# Audio.net
KiCad netlist of a schematic drawn in Altium Designer
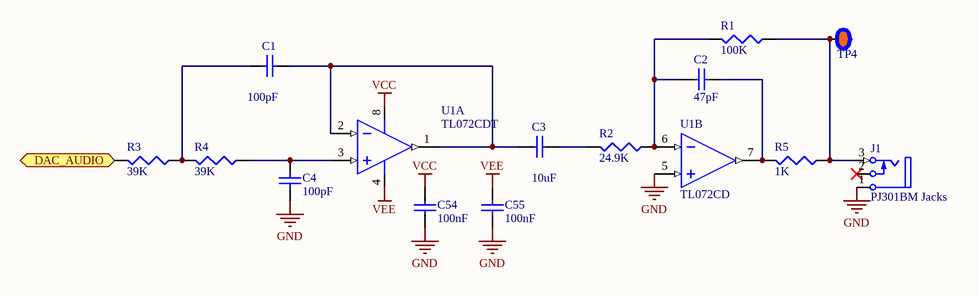
[diagram p0: Audio.SchDoc]

(export (version "E")
  (design (tool "Eeschema 10.0.6"))
  (components
    (comp (ref "C1")
      (value "100pF")
      (footprint "RES_0603")
      (description "Capacitor")
      (fields
        (field (name "MANUFACTURER") "Yageo")
        (field (name "MANUFACTURER PART NUMBER") "CC0603JRNPO9BN101")
      )
      (libsource (lib "Miscellaneous Devices") (part "Cap"))
    )
    (comp (ref "C2")
      (value "47pF")
      (footprint "RES_0603")
      (description "Capacitor")
      (fields
        (field (name "MANUFACTURER") "AVX Corporation")
        (field (name "MANUFACTURER PART NUMBER") "06031A470FAT2A")
      )
      (libsource (lib "Miscellaneous Devices") (part "Cap"))
    )
    (comp (ref "C3")
      (value "10uF")
      (footprint "RES_1206")
      (description "Capacitor")
      (fields
        (field (name "MANUFACTURER") "Murata")
        (field (name "MANUFACTURER PART NUMBER") "GRT31CR61H106ME01L")
      )
      (libsource (lib "Miscellaneous Devices") (part "Cap"))
    )
    (comp (ref "C4")
      (value "100pF")
      (footprint "RES_0603")
      (description "Capacitor")
      (fields
        (field (name "MANUFACTURER") "Yageo")
        (field (name "MANUFACTURER PART NUMBER") "CC0603JRNPO9BN101")
      )
      (libsource (lib "Miscellaneous Devices") (part "Cap"))
    )
    (comp (ref "C54")
      (value "100nF")
      (footprint "RES_0603")
      (description "Capacitor")
      (fields
        (field (name "MANUFACTURER") "AVX Corporation")
        (field (name "MANUFACTURER PART NUMBER") "06035G104ZAT2A")
      )
      (libsource (lib "Miscellaneous Devices") (part "Cap"))
    )
    (comp (ref "C55")
      (value "100nF")
      (footprint "RES_0603")
      (description "Capacitor")
      (fields
        (field (name "MANUFACTURER") "AVX Corporation")
        (field (name "MANUFACTURER PART NUMBER") "06035G104ZAT2A")
      )
      (libsource (lib "Miscellaneous Devices") (part "Cap"))
    )
    (comp (ref "J1")
      (value "PJ301BM Jacks")
      (footprint "WQP-PJ301M-12_JACK")
      (description "Jack Socket, 1/4\" [6.5mm], Thru-Hole, Vertical, 2-Conductor with Tip closed")
      (fields (field (name "MANUFACTURER") "Thonkiconn"))
      (libsource (lib "Miscellaneous Connectors") (part "Phonejack2 TN"))
    )
    (comp (ref "R1")
      (value "100K")
      (footprint "RES_0603")
      (description "Resistor")
      (fields
        (field (name "MANUFACTURER") "Susumu")
        (field (name "MANUFACTURER PART NUMBER") "RR0816P-104-D")
      )
      (libsource (lib "Miscellaneous Devices") (part "Res3"))
    )
    (comp (ref "R2")
      (value "24.9K")
      (footprint "RES_0603")
      (description "ERA-3AEB2492V")
      (fields (field (name "MANUFACTURER") "Panasonic Electronic Components"))
      (libsource (lib "Miscellaneous Devices") (part "Res3"))
    )
    (comp (ref "R3")
      (value "39K")
      (footprint "RES_0603")
      (description "ERA-3AEB393V")
      (fields (field (name "MANUFACTURER") "Panasonic Electronic Components"))
      (libsource (lib "Miscellaneous Devices") (part "Res3"))
    )
    (comp (ref "R4")
      (value "39K")
      (footprint "RES_0603")
      (description "ERA-3AEB393V")
      (fields (field (name "MANUFACTURER") "Panasonic Electronic Components"))
      (libsource (lib "Miscellaneous Devices") (part "Res3"))
    )
    (comp (ref "R5")
      (value "1K")
      (footprint "RES_0603")
      (description "Resistor")
      (fields
        (field (name "MANUFACTURER") "Susumu")
        (field (name "MANUFACTURER PART NUMBER") "RR0816P-102-D")
      )
      (libsource (lib "Miscellaneous Devices") (part "Res3"))
    )
    (comp (ref "TP4")
      (value "loop test point")
      (footprint "Test Point Mt Hole")
      (description "Test Point Loop Miniature Keysone")
      (fields
        (field (name "MANUFACTURER") "Keystone Electronics")
        (field (name "MANUFACTURER PART NUMBER") "5003")
      )
      (libsource (lib "Custom") (part "Test Point"))
    )
    (comp (ref "U1")
      (value "TL072CD")
      (footprint "TI-D8_N")
      (description "IC OPAMP JFET 4MHZ 8SO")
      (fields
        (field (name "MANUFACTURER") "STMicroelectronics")
        (field (name "MANUFACTURER PART NUMBER") "TL072CDT")
      )
      (libsource (lib "Custom") (part "TL072CD"))
    )
  )
  (nets
    (net (code "1") (name "/DAC_AUDIO") (class "Default")
      (node (ref "R3") (pin "2") (pinfunction "2_2") (pintype "passive"))
    )
    (net (code "2") (name "GND") (class "Default")
      (node (ref "C4") (pin "1") (pinfunction "1_1") (pintype "passive"))
      (node (ref "C54") (pin "1") (pinfunction "1_1") (pintype "passive"))
      (node (ref "C55") (pin "1") (pinfunction "1_1") (pintype "passive"))
      (node (ref "J1") (pin "1") (pinfunction "S_1") (pintype "power_in"))
      (node (ref "U1") (pin "5") (pinfunction "IN2+_5") (pintype "input"))
    )
    (net (code "3") (name "Net-(C1-Pad1)") (class "Default")
      (node (ref "C1") (pin "1") (pinfunction "1_1") (pintype "passive"))
      (node (ref "R3") (pin "1") (pinfunction "1_1") (pintype "passive"))
      (node (ref "R4") (pin "2") (pinfunction "2_2") (pintype "passive"))
    )
    (net (code "4") (name "Net-(C3-Pad2)") (class "Default")
      (node (ref "C3") (pin "2") (pinfunction "2_2") (pintype "passive"))
      (node (ref "R2") (pin "2") (pinfunction "2_2") (pintype "passive"))
    )
    (net (code "5") (name "Net-(J1-T)") (class "Default")
      (node (ref "J1") (pin "3") (pinfunction "T_3") (pintype "input"))
      (node (ref "R1") (pin "1") (pinfunction "1_1") (pintype "passive"))
      (node (ref "R5") (pin "1") (pinfunction "1_1") (pintype "passive"))
      (node (ref "TP4") (pin "1") (pinfunction "1_1") (pintype "passive"))
    )
    (net (code "6") (name "Net-(U1A-IN1+)") (class "Default")
      (node (ref "C4") (pin "2") (pinfunction "2_2") (pintype "passive"))
      (node (ref "R4") (pin "1") (pinfunction "1_1") (pintype "passive"))
      (node (ref "U1") (pin "3") (pinfunction "IN1+_3") (pintype "input"))
    )
    (net (code "7") (name "Net-(U1A-IN1-)") (class "Default")
      (node (ref "C1") (pin "2") (pinfunction "2_2") (pintype "passive"))
      (node (ref "C3") (pin "1") (pinfunction "1_1") (pintype "passive"))
      (node (ref "U1") (pin "1") (pinfunction "OUT1_1") (pintype "output"))
      (node (ref "U1") (pin "2") (pinfunction "IN1-_2") (pintype "input"))
    )
    (net (code "8") (name "Net-(U1B-IN2-)") (class "Default")
      (node (ref "C2") (pin "2") (pinfunction "2_2") (pintype "passive"))
      (node (ref "R1") (pin "2") (pinfunction "2_2") (pintype "passive"))
      (node (ref "R2") (pin "1") (pinfunction "1_1") (pintype "passive"))
      (node (ref "U1") (pin "6") (pinfunction "IN2-_6") (pintype "input"))
    )
    (net (code "9") (name "Net-(U1B-OUT2)") (class "Default")
      (node (ref "C2") (pin "1") (pinfunction "1_1") (pintype "passive"))
      (node (ref "R5") (pin "2") (pinfunction "2_2") (pintype "passive"))
      (node (ref "U1") (pin "7") (pinfunction "OUT2_7") (pintype "output"))
    )
    (net (code "10") (name "VCC") (class "Default")
      (node (ref "C54") (pin "2") (pinfunction "2_2") (pintype "passive"))
      (node (ref "U1") (pin "8") (pinfunction "V+_8") (pintype "passive"))
    )
    (net (code "11") (name "VEE") (class "Default")
      (node (ref "C55") (pin "2") (pinfunction "2_2") (pintype "passive"))
      (node (ref "U1") (pin "4") (pinfunction "V-_4") (pintype "passive"))
    )
    (net (code "12") (name "unconnected-(J1-TN-Pad2)") (class "Default")
      (node (ref "J1") (pin "2") (pinfunction "TN_2") (pintype "passive+no_connect"))
    )
  )
)
